# Interfaces.net
KiCad netlist of a schematic drawn in Altium Designer
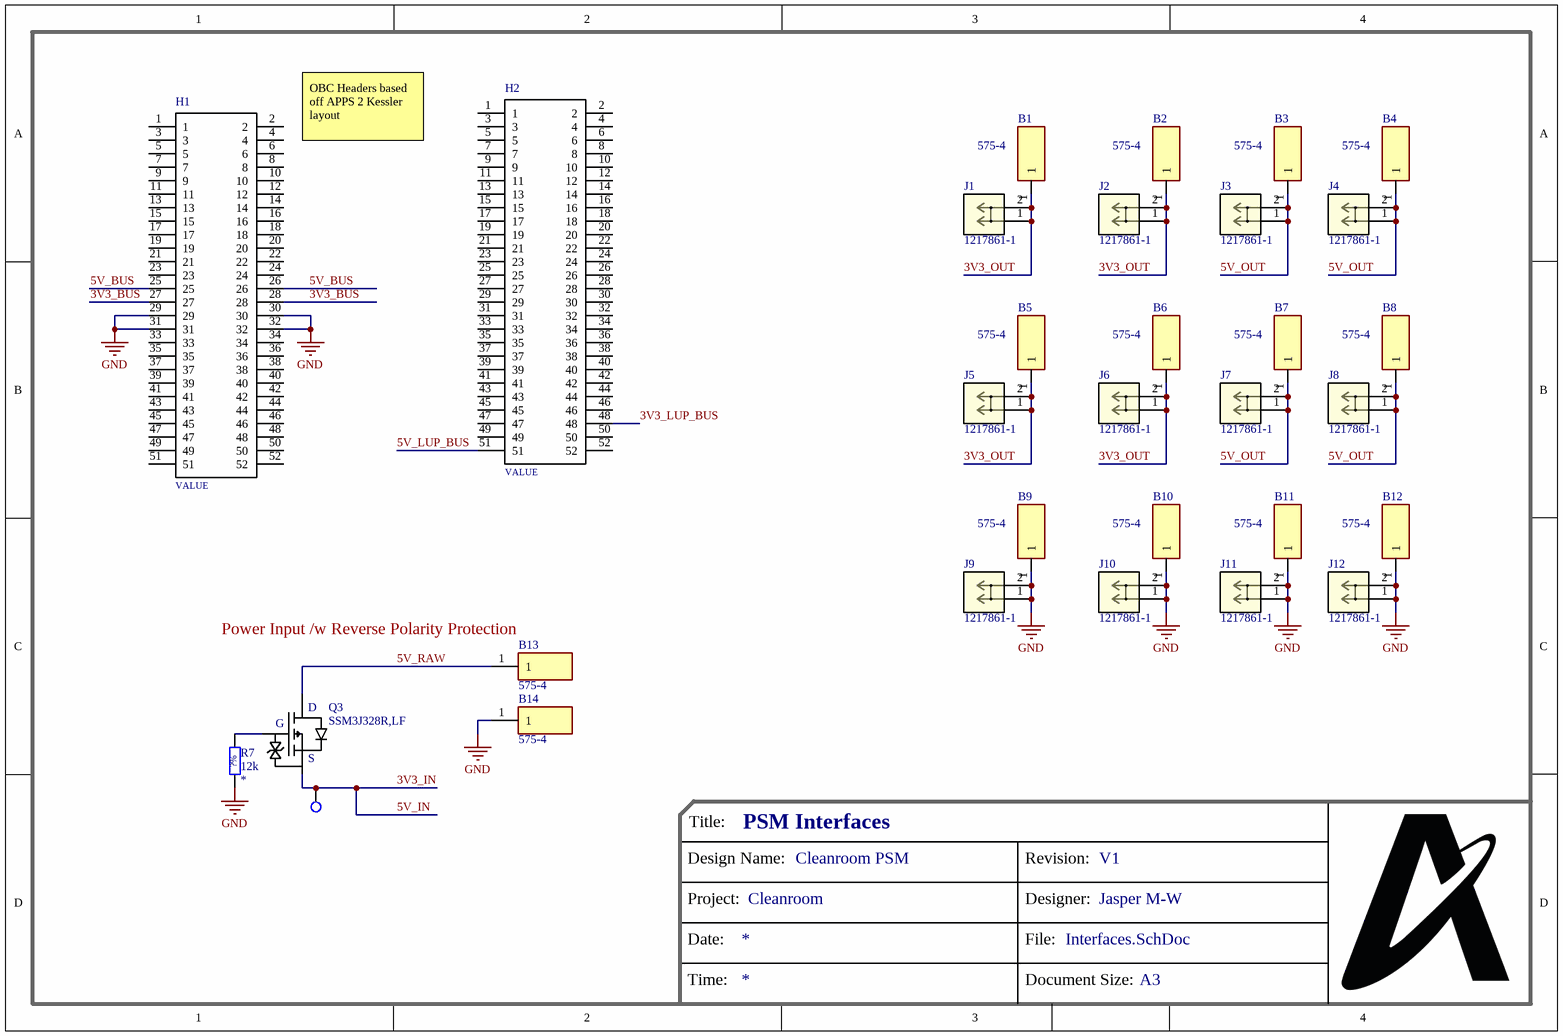
[diagram p0: Interfaces.SchDoc]

(export (version "E")
  (design (tool "Eeschema 10.0.6"))
  (components
    (comp (ref "B1")
      (value "575-4")
      (footprint "5754")
      (description "Test Plugs & Test Jacks NON-INSUL JACK .218\" BRASS NICKEL PLTD")
      (fields (field (name "MOUSER PART NUMBER") "534-575-4"))
      (libsource (lib "575-4") (part "575-4"))
    )
    (comp (ref "B2")
      (value "575-4")
      (footprint "5754")
      (description "Test Plugs & Test Jacks NON-INSUL JACK .218\" BRASS NICKEL PLTD")
      (fields (field (name "MOUSER PART NUMBER") "534-575-4"))
      (libsource (lib "575-4") (part "575-4"))
    )
    (comp (ref "B3")
      (value "575-4")
      (footprint "5754")
      (description "Test Plugs & Test Jacks NON-INSUL JACK .218\" BRASS NICKEL PLTD")
      (fields (field (name "MOUSER PART NUMBER") "534-575-4"))
      (libsource (lib "575-4") (part "575-4"))
    )
    (comp (ref "B4")
      (value "575-4")
      (footprint "5754")
      (description "Test Plugs & Test Jacks NON-INSUL JACK .218\" BRASS NICKEL PLTD")
      (fields (field (name "MOUSER PART NUMBER") "534-575-4"))
      (libsource (lib "575-4") (part "575-4"))
    )
    (comp (ref "B5")
      (value "575-4")
      (footprint "5754")
      (description "Test Plugs & Test Jacks NON-INSUL JACK .218\" BRASS NICKEL PLTD")
      (fields (field (name "MOUSER PART NUMBER") "534-575-4"))
      (libsource (lib "575-4") (part "575-4"))
    )
    (comp (ref "B6")
      (value "575-4")
      (footprint "5754")
      (description "Test Plugs & Test Jacks NON-INSUL JACK .218\" BRASS NICKEL PLTD")
      (fields (field (name "MOUSER PART NUMBER") "534-575-4"))
      (libsource (lib "575-4") (part "575-4"))
    )
    (comp (ref "B7")
      (value "575-4")
      (footprint "5754")
      (description "Test Plugs & Test Jacks NON-INSUL JACK .218\" BRASS NICKEL PLTD")
      (fields (field (name "MOUSER PART NUMBER") "534-575-4"))
      (libsource (lib "575-4") (part "575-4"))
    )
    (comp (ref "B8")
      (value "575-4")
      (footprint "5754")
      (description "Test Plugs & Test Jacks NON-INSUL JACK .218\" BRASS NICKEL PLTD")
      (fields (field (name "MOUSER PART NUMBER") "534-575-4"))
      (libsource (lib "575-4") (part "575-4"))
    )
    (comp (ref "B9")
      (value "575-4")
      (footprint "5754")
      (description "Test Plugs & Test Jacks NON-INSUL JACK .218\" BRASS NICKEL PLTD")
      (fields (field (name "MOUSER PART NUMBER") "534-575-4"))
      (libsource (lib "575-4") (part "575-4"))
    )
    (comp (ref "B10")
      (value "575-4")
      (footprint "5754")
      (description "Test Plugs & Test Jacks NON-INSUL JACK .218\" BRASS NICKEL PLTD")
      (fields (field (name "MOUSER PART NUMBER") "534-575-4"))
      (libsource (lib "575-4") (part "575-4"))
    )
    (comp (ref "B11")
      (value "575-4")
      (footprint "5754")
      (description "Test Plugs & Test Jacks NON-INSUL JACK .218\" BRASS NICKEL PLTD")
      (fields (field (name "MOUSER PART NUMBER") "534-575-4"))
      (libsource (lib "575-4") (part "575-4"))
    )
    (comp (ref "B12")
      (value "575-4")
      (footprint "5754")
      (description "Test Plugs & Test Jacks NON-INSUL JACK .218\" BRASS NICKEL PLTD")
      (fields (field (name "MOUSER PART NUMBER") "534-575-4"))
      (libsource (lib "575-4") (part "575-4"))
    )
    (comp (ref "B13")
      (value "575-4")
      (footprint "5754")
      (description "Test Plugs & Test Jacks NON-INSUL JACK .218\" BRASS NICKEL PLTD")
      (fields (field (name "MOUSER PART NUMBER") "534-575-4"))
      (libsource (lib "") (part "575-4_1"))
    )
    (comp (ref "B14")
      (value "575-4")
      (footprint "5754")
      (description "Test Plugs & Test Jacks NON-INSUL JACK .218\" BRASS NICKEL PLTD")
      (fields (field (name "MOUSER PART NUMBER") "534-575-4"))
      (libsource (lib "") (part "575-4_1"))
    )
    (comp (ref "H1")
      (value "ESQ-126-14-G-D")
      (footprint "*SAMTEC_ESQ-126-14-G-D")
      (fields (field (name "MF") "Samtec Inc."))
      (libsource (lib "ESQ-126-14-G-D") (part "ESQ-126-14-G-D"))
    )
    (comp (ref "H2")
      (value "ESQ-126-14-G-D")
      (footprint "*SAMTEC_ESQ-126-14-G-D")
      (fields (field (name "MF") "Samtec Inc."))
      (libsource (lib "ESQ-126-14-G-D") (part "ESQ-126-14-G-D"))
    )
    (comp (ref "J1")
      (value "1217861-1")
      (footprint "CONN_1217861-1_TEC")
      (description "250 FASTON,PCB TAB,TCBR")
      (fields (field (name "COPYRIGHT") "Copyright (C) 2025 Ultra Librarian. All rights reserved."))
      (libsource (lib "1217861-1") (part "1217861-1"))
    )
    (comp (ref "J2")
      (value "1217861-1")
      (footprint "CONN_1217861-1_TEC")
      (description "250 FASTON,PCB TAB,TCBR")
      (fields (field (name "COPYRIGHT") "Copyright (C) 2025 Ultra Librarian. All rights reserved."))
      (libsource (lib "1217861-1") (part "1217861-1"))
    )
    (comp (ref "J3")
      (value "1217861-1")
      (footprint "CONN_1217861-1_TEC")
      (description "250 FASTON,PCB TAB,TCBR")
      (fields (field (name "COPYRIGHT") "Copyright (C) 2025 Ultra Librarian. All rights reserved."))
      (libsource (lib "1217861-1") (part "1217861-1"))
    )
    (comp (ref "J4")
      (value "1217861-1")
      (footprint "CONN_1217861-1_TEC")
      (description "250 FASTON,PCB TAB,TCBR")
      (fields (field (name "COPYRIGHT") "Copyright (C) 2025 Ultra Librarian. All rights reserved."))
      (libsource (lib "1217861-1") (part "1217861-1"))
    )
    (comp (ref "J5")
      (value "1217861-1")
      (footprint "CONN_1217861-1_TEC")
      (description "250 FASTON,PCB TAB,TCBR")
      (fields (field (name "COPYRIGHT") "Copyright (C) 2025 Ultra Librarian. All rights reserved."))
      (libsource (lib "1217861-1") (part "1217861-1"))
    )
    (comp (ref "J6")
      (value "1217861-1")
      (footprint "CONN_1217861-1_TEC")
      (description "250 FASTON,PCB TAB,TCBR")
      (fields (field (name "COPYRIGHT") "Copyright (C) 2025 Ultra Librarian. All rights reserved."))
      (libsource (lib "1217861-1") (part "1217861-1"))
    )
    (comp (ref "J7")
      (value "1217861-1")
      (footprint "CONN_1217861-1_TEC")
      (description "250 FASTON,PCB TAB,TCBR")
      (fields (field (name "COPYRIGHT") "Copyright (C) 2025 Ultra Librarian. All rights reserved."))
      (libsource (lib "1217861-1") (part "1217861-1"))
    )
    (comp (ref "J8")
      (value "1217861-1")
      (footprint "CONN_1217861-1_TEC")
      (description "250 FASTON,PCB TAB,TCBR")
      (fields (field (name "COPYRIGHT") "Copyright (C) 2025 Ultra Librarian. All rights reserved."))
      (libsource (lib "1217861-1") (part "1217861-1"))
    )
    (comp (ref "J9")
      (value "1217861-1")
      (footprint "CONN_1217861-1_TEC")
      (description "250 FASTON,PCB TAB,TCBR")
      (fields (field (name "COPYRIGHT") "Copyright (C) 2025 Ultra Librarian. All rights reserved."))
      (libsource (lib "1217861-1") (part "1217861-1"))
    )
    (comp (ref "J10")
      (value "1217861-1")
      (footprint "CONN_1217861-1_TEC")
      (description "250 FASTON,PCB TAB,TCBR")
      (fields (field (name "COPYRIGHT") "Copyright (C) 2025 Ultra Librarian. All rights reserved."))
      (libsource (lib "1217861-1") (part "1217861-1"))
    )
    (comp (ref "J11")
      (value "1217861-1")
      (footprint "CONN_1217861-1_TEC")
      (description "250 FASTON,PCB TAB,TCBR")
      (fields (field (name "COPYRIGHT") "Copyright (C) 2025 Ultra Librarian. All rights reserved."))
      (libsource (lib "1217861-1") (part "1217861-1"))
    )
    (comp (ref "J12")
      (value "1217861-1")
      (footprint "CONN_1217861-1_TEC")
      (description "250 FASTON,PCB TAB,TCBR")
      (fields (field (name "COPYRIGHT") "Copyright (C) 2025 Ultra Librarian. All rights reserved."))
      (libsource (lib "1217861-1") (part "1217861-1"))
    )
    (comp (ref "Q3")
      (value "SSM3J328R,LF")
      (footprint "APSS Prototype Parts:SOT23F-3-0.8mm")
      (description "Transistor - MOSFET, P-Channel SSM3J328R,LF")
      (fields (field (name "POWER") "1W") (field (name "APSS STANDARD PART") "APSS Standard"))
      (libsource (lib "APSS Prototype Parts") (part "SSM3J328R,LF"))
    )
    (comp (ref "R7")
      (value "12k")
      (footprint "RESISTOR_0805_2012M-50N")
      (description "Passive - Resistor, Generic")
      (fields (field (name "TOLERANCE") "?%") (field (name "MF PART NO.") "*"))
      (libsource (lib "APSS Generic Components (3)") (part "Generic Resistor"))
    )
    (comp (ref "T1")
      (value "Test Pad")
      (footprint "APSS Generic Components:Test Pad")
      (libsource (lib "APSS Generic Components") (part "Test Pad"))
    )
  )
  (nets
    (net (code "1") (name "/3V3_BUS") (class "Default")
      (node (ref "H1") (pin "27") (pinfunction "27_27") (pintype "passive"))
      (node (ref "H1") (pin "28") (pinfunction "28_28") (pintype "passive"))
    )
    (net (code "2") (name "/3V3_IN") (class "Default")
      (node (ref "Q3") (pin "2") (pinfunction "S_2") (pintype "passive"))
      (node (ref "T1") (pin "1") (pinfunction "0_1") (pintype "passive"))
    )
    (net (code "3") (name "/3V3_LUP_BUS") (class "Default")
      (node (ref "H2") (pin "48") (pinfunction "48_48") (pintype "passive"))
    )
    (net (code "4") (name "/3V3_OUT") (class "Default")
      (node (ref "B1") (pin "1") (pinfunction "1_1") (pintype "passive"))
      (node (ref "B2") (pin "1") (pinfunction "1_1") (pintype "passive"))
      (node (ref "B5") (pin "1") (pinfunction "1_1") (pintype "passive"))
      (node (ref "B6") (pin "1") (pinfunction "1_1") (pintype "passive"))
      (node (ref "J1") (pin "1") (pinfunction "1_1") (pintype "passive"))
      (node (ref "J1") (pin "2") (pinfunction "2_2") (pintype "passive"))
      (node (ref "J2") (pin "1") (pinfunction "1_1") (pintype "passive"))
      (node (ref "J2") (pin "2") (pinfunction "2_2") (pintype "passive"))
      (node (ref "J5") (pin "1") (pinfunction "1_1") (pintype "passive"))
      (node (ref "J5") (pin "2") (pinfunction "2_2") (pintype "passive"))
      (node (ref "J6") (pin "1") (pinfunction "1_1") (pintype "passive"))
      (node (ref "J6") (pin "2") (pinfunction "2_2") (pintype "passive"))
    )
    (net (code "5") (name "/5V_BUS") (class "Default")
      (node (ref "H1") (pin "25") (pinfunction "25_25") (pintype "passive"))
      (node (ref "H1") (pin "26") (pinfunction "26_26") (pintype "passive"))
    )
    (net (code "6") (name "/5V_LUP_BUS") (class "Default")
      (node (ref "H2") (pin "51") (pinfunction "51_51") (pintype "passive"))
    )
    (net (code "7") (name "/5V_OUT") (class "Default")
      (node (ref "B3") (pin "1") (pinfunction "1_1") (pintype "passive"))
      (node (ref "B4") (pin "1") (pinfunction "1_1") (pintype "passive"))
      (node (ref "B7") (pin "1") (pinfunction "1_1") (pintype "passive"))
      (node (ref "B8") (pin "1") (pinfunction "1_1") (pintype "passive"))
      (node (ref "J3") (pin "1") (pinfunction "1_1") (pintype "passive"))
      (node (ref "J3") (pin "2") (pinfunction "2_2") (pintype "passive"))
      (node (ref "J4") (pin "1") (pinfunction "1_1") (pintype "passive"))
      (node (ref "J4") (pin "2") (pinfunction "2_2") (pintype "passive"))
      (node (ref "J7") (pin "1") (pinfunction "1_1") (pintype "passive"))
      (node (ref "J7") (pin "2") (pinfunction "2_2") (pintype "passive"))
      (node (ref "J8") (pin "1") (pinfunction "1_1") (pintype "passive"))
      (node (ref "J8") (pin "2") (pinfunction "2_2") (pintype "passive"))
    )
    (net (code "8") (name "/5V_RAW") (class "Default")
      (node (ref "B13") (pin "1") (pinfunction "1_1") (pintype "passive"))
      (node (ref "Q3") (pin "3") (pinfunction "D_3") (pintype "passive"))
    )
    (net (code "9") (name "GND") (class "Default")
      (node (ref "B10") (pin "1") (pinfunction "1_1") (pintype "passive"))
      (node (ref "B11") (pin "1") (pinfunction "1_1") (pintype "passive"))
      (node (ref "B12") (pin "1") (pinfunction "1_1") (pintype "passive"))
      (node (ref "B14") (pin "1") (pinfunction "1_1") (pintype "passive"))
      (node (ref "B9") (pin "1") (pinfunction "1_1") (pintype "passive"))
      (node (ref "H1") (pin "29") (pinfunction "29_29") (pintype "passive"))
      (node (ref "H1") (pin "30") (pinfunction "30_30") (pintype "passive"))
      (node (ref "H1") (pin "31") (pinfunction "31_31") (pintype "passive"))
      (node (ref "H1") (pin "32") (pinfunction "32_32") (pintype "passive"))
      (node (ref "J10") (pin "1") (pinfunction "1_1") (pintype "passive"))
      (node (ref "J10") (pin "2") (pinfunction "2_2") (pintype "passive"))
      (node (ref "J11") (pin "1") (pinfunction "1_1") (pintype "passive"))
      (node (ref "J11") (pin "2") (pinfunction "2_2") (pintype "passive"))
      (node (ref "J12") (pin "1") (pinfunction "1_1") (pintype "passive"))
      (node (ref "J12") (pin "2") (pinfunction "2_2") (pintype "passive"))
      (node (ref "J9") (pin "1") (pinfunction "1_1") (pintype "passive"))
      (node (ref "J9") (pin "2") (pinfunction "2_2") (pintype "passive"))
      (node (ref "R7") (pin "1") (pinfunction "1_1") (pintype "passive"))
    )
    (net (code "10") (name "Net-(Q3-G)") (class "Default")
      (node (ref "Q3") (pin "1") (pinfunction "G_1") (pintype "passive"))
      (node (ref "R7") (pin "2") (pinfunction "2_2") (pintype "passive"))
    )
    (net (code "11") (name "unconnected-(H1-Pad1)") (class "Default")
      (node (ref "H1") (pin "1") (pinfunction "1_1") (pintype "passive"))
    )
    (net (code "12") (name "unconnected-(H1-Pad2)") (class "Default")
      (node (ref "H1") (pin "2") (pinfunction "2_2") (pintype "passive"))
    )
    (net (code "13") (name "unconnected-(H1-Pad3)") (class "Default")
      (node (ref "H1") (pin "3") (pinfunction "3_3") (pintype "passive"))
    )
    (net (code "14") (name "unconnected-(H1-Pad4)") (class "Default")
      (node (ref "H1") (pin "4") (pinfunction "4_4") (pintype "passive"))
    )
    (net (code "15") (name "unconnected-(H1-Pad5)") (class "Default")
      (node (ref "H1") (pin "5") (pinfunction "5_5") (pintype "passive"))
    )
    (net (code "16") (name "unconnected-(H1-Pad6)") (class "Default")
      (node (ref "H1") (pin "6") (pinfunction "6_6") (pintype "passive"))
    )
    (net (code "17") (name "unconnected-(H1-Pad7)") (class "Default")
      (node (ref "H1") (pin "7") (pinfunction "7_7") (pintype "passive"))
    )
    (net (code "18") (name "unconnected-(H1-Pad8)") (class "Default")
      (node (ref "H1") (pin "8") (pinfunction "8_8") (pintype "passive"))
    )
    (net (code "19") (name "unconnected-(H1-Pad9)") (class "Default")
      (node (ref "H1") (pin "9") (pinfunction "9_9") (pintype "passive"))
    )
    (net (code "20") (name "unconnected-(H1-Pad10)") (class "Default")
      (node (ref "H1") (pin "10") (pinfunction "10_10") (pintype "passive"))
    )
    (net (code "21") (name "unconnected-(H1-Pad11)") (class "Default")
      (node (ref "H1") (pin "11") (pinfunction "11_11") (pintype "passive"))
    )
    (net (code "22") (name "unconnected-(H1-Pad12)") (class "Default")
      (node (ref "H1") (pin "12") (pinfunction "12_12") (pintype "passive"))
    )
    (net (code "23") (name "unconnected-(H1-Pad13)") (class "Default")
      (node (ref "H1") (pin "13") (pinfunction "13_13") (pintype "passive"))
    )
    (net (code "24") (name "unconnected-(H1-Pad14)") (class "Default")
      (node (ref "H1") (pin "14") (pinfunction "14_14") (pintype "passive"))
    )
    (net (code "25") (name "unconnected-(H1-Pad15)") (class "Default")
      (node (ref "H1") (pin "15") (pinfunction "15_15") (pintype "passive"))
    )
    (net (code "26") (name "unconnected-(H1-Pad16)") (class "Default")
      (node (ref "H1") (pin "16") (pinfunction "16_16") (pintype "passive"))
    )
    (net (code "27") (name "unconnected-(H1-Pad17)") (class "Default")
      (node (ref "H1") (pin "17") (pinfunction "17_17") (pintype "passive"))
    )
    (net (code "28") (name "unconnected-(H1-Pad18)") (class "Default")
      (node (ref "H1") (pin "18") (pinfunction "18_18") (pintype "passive"))
    )
    (net (code "29") (name "unconnected-(H1-Pad19)") (class "Default")
      (node (ref "H1") (pin "19") (pinfunction "19_19") (pintype "passive"))
    )
    (net (code "30") (name "unconnected-(H1-Pad20)") (class "Default")
      (node (ref "H1") (pin "20") (pinfunction "20_20") (pintype "passive"))
    )
    (net (code "31") (name "unconnected-(H1-Pad21)") (class "Default")
      (node (ref "H1") (pin "21") (pinfunction "21_21") (pintype "passive"))
    )
    (net (code "32") (name "unconnected-(H1-Pad22)") (class "Default")
      (node (ref "H1") (pin "22") (pinfunction "22_22") (pintype "passive"))
    )
    (net (code "33") (name "unconnected-(H1-Pad23)") (class "Default")
      (node (ref "H1") (pin "23") (pinfunction "23_23") (pintype "passive"))
    )
    (net (code "34") (name "unconnected-(H1-Pad24)") (class "Default")
      (node (ref "H1") (pin "24") (pinfunction "24_24") (pintype "passive"))
    )
    (net (code "35") (name "unconnected-(H1-Pad33)") (class "Default")
      (node (ref "H1") (pin "33") (pinfunction "33_33") (pintype "passive"))
    )
    (net (code "36") (name "unconnected-(H1-Pad34)") (class "Default")
      (node (ref "H1") (pin "34") (pinfunction "34_34") (pintype "passive"))
    )
    (net (code "37") (name "unconnected-(H1-Pad35)") (class "Default")
      (node (ref "H1") (pin "35") (pinfunction "35_35") (pintype "passive"))
    )
    (net (code "38") (name "unconnected-(H1-Pad36)") (class "Default")
      (node (ref "H1") (pin "36") (pinfunction "36_36") (pintype "passive"))
    )
    (net (code "39") (name "unconnected-(H1-Pad37)") (class "Default")
      (node (ref "H1") (pin "37") (pinfunction "37_37") (pintype "passive"))
    )
    (net (code "40") (name "unconnected-(H1-Pad38)") (class "Default")
      (node (ref "H1") (pin "38") (pinfunction "38_38") (pintype "passive"))
    )
    (net (code "41") (name "unconnected-(H1-Pad39)") (class "Default")
      (node (ref "H1") (pin "39") (pinfunction "39_39") (pintype "passive"))
    )
    (net (code "42") (name "unconnected-(H1-Pad40)") (class "Default")
      (node (ref "H1") (pin "40") (pinfunction "40_40") (pintype "passive"))
    )
    (net (code "43") (name "unconnected-(H1-Pad41)") (class "Default")
      (node (ref "H1") (pin "41") (pinfunction "41_41") (pintype "passive"))
    )
    (net (code "44") (name "unconnected-(H1-Pad42)") (class "Default")
      (node (ref "H1") (pin "42") (pinfunction "42_42") (pintype "passive"))
    )
    (net (code "45") (name "unconnected-(H1-Pad43)") (class "Default")
      (node (ref "H1") (pin "43") (pinfunction "43_43") (pintype "passive"))
    )
    (net (code "46") (name "unconnected-(H1-Pad44)") (class "Default")
      (node (ref "H1") (pin "44") (pinfunction "44_44") (pintype "passive"))
    )
    (net (code "47") (name "unconnected-(H1-Pad45)") (class "Default")
      (node (ref "H1") (pin "45") (pinfunction "45_45") (pintype "passive"))
    )
    (net (code "48") (name "unconnected-(H1-Pad46)") (class "Default")
      (node (ref "H1") (pin "46") (pinfunction "46_46") (pintype "passive"))
    )
    (net (code "49") (name "unconnected-(H1-Pad47)") (class "Default")
      (node (ref "H1") (pin "47") (pinfunction "47_47") (pintype "passive"))
    )
    (net (code "50") (name "unconnected-(H1-Pad48)") (class "Default")
      (node (ref "H1") (pin "48") (pinfunction "48_48") (pintype "passive"))
    )
    (net (code "51") (name "unconnected-(H1-Pad49)") (class "Default")
      (node (ref "H1") (pin "49") (pinfunction "49_49") (pintype "passive"))
    )
    (net (code "52") (name "unconnected-(H1-Pad50)") (class "Default")
      (node (ref "H1") (pin "50") (pinfunction "50_50") (pintype "passive"))
    )
    (net (code "53") (name "unconnected-(H1-Pad51)") (class "Default")
      (node (ref "H1") (pin "51") (pinfunction "51_51") (pintype "passive"))
    )
    (net (code "54") (name "unconnected-(H1-Pad52)") (class "Default")
      (node (ref "H1") (pin "52") (pinfunction "52_52") (pintype "passive"))
    )
    (net (code "55") (name "unconnected-(H2-Pad1)") (class "Default")
      (node (ref "H2") (pin "1") (pinfunction "1_1") (pintype "passive"))
    )
    (net (code "56") (name "unconnected-(H2-Pad2)") (class "Default")
      (node (ref "H2") (pin "2") (pinfunction "2_2") (pintype "passive"))
    )
    (net (code "57") (name "unconnected-(H2-Pad3)") (class "Default")
      (node (ref "H2") (pin "3") (pinfunction "3_3") (pintype "passive"))
    )
    (net (code "58") (name "unconnected-(H2-Pad4)") (class "Default")
      (node (ref "H2") (pin "4") (pinfunction "4_4") (pintype "passive"))
    )
    (net (code "59") (name "unconnected-(H2-Pad5)") (class "Default")
      (node (ref "H2") (pin "5") (pinfunction "5_5") (pintype "passive"))
    )
    (net (code "60") (name "unconnected-(H2-Pad6)") (class "Default")
      (node (ref "H2") (pin "6") (pinfunction "6_6") (pintype "passive"))
    )
    (net (code "61") (name "unconnected-(H2-Pad7)") (class "Default")
      (node (ref "H2") (pin "7") (pinfunction "7_7") (pintype "passive"))
    )
    (net (code "62") (name "unconnected-(H2-Pad8)") (class "Default")
      (node (ref "H2") (pin "8") (pinfunction "8_8") (pintype "passive"))
    )
    (net (code "63") (name "unconnected-(H2-Pad9)") (class "Default")
      (node (ref "H2") (pin "9") (pinfunction "9_9") (pintype "passive"))
    )
    (net (code "64") (name "unconnected-(H2-Pad10)") (class "Default")
      (node (ref "H2") (pin "10") (pinfunction "10_10") (pintype "passive"))
    )
    (net (code "65") (name "unconnected-(H2-Pad11)") (class "Default")
      (node (ref "H2") (pin "11") (pinfunction "11_11") (pintype "passive"))
    )
    (net (code "66") (name "unconnected-(H2-Pad12)") (class "Default")
      (node (ref "H2") (pin "12") (pinfunction "12_12") (pintype "passive"))
    )
    (net (code "67") (name "unconnected-(H2-Pad13)") (class "Default")
      (node (ref "H2") (pin "13") (pinfunction "13_13") (pintype "passive"))
    )
    (net (code "68") (name "unconnected-(H2-Pad14)") (class "Default")
      (node (ref "H2") (pin "14") (pinfunction "14_14") (pintype "passive"))
    )
    (net (code "69") (name "unconnected-(H2-Pad15)") (class "Default")
      (node (ref "H2") (pin "15") (pinfunction "15_15") (pintype "passive"))
    )
    (net (code "70") (name "unconnected-(H2-Pad16)") (class "Default")
      (node (ref "H2") (pin "16") (pinfunction "16_16") (pintype "passive"))
    )
    (net (code "71") (name "unconnected-(H2-Pad17)") (class "Default")
      (node (ref "H2") (pin "17") (pinfunction "17_17") (pintype "passive"))
    )
    (net (code "72") (name "unconnected-(H2-Pad18)") (class "Default")
      (node (ref "H2") (pin "18") (pinfunction "18_18") (pintype "passive"))
    )
    (net (code "73") (name "unconnected-(H2-Pad19)") (class "Default")
      (node (ref "H2") (pin "19") (pinfunction "19_19") (pintype "passive"))
    )
    (net (code "74") (name "unconnected-(H2-Pad20)") (class "Default")
      (node (ref "H2") (pin "20") (pinfunction "20_20") (pintype "passive"))
    )
    (net (code "75") (name "unconnected-(H2-Pad21)") (class "Default")
      (node (ref "H2") (pin "21") (pinfunction "21_21") (pintype "passive"))
    )
    (net (code "76") (name "unconnected-(H2-Pad22)") (class "Default")
      (node (ref "H2") (pin "22") (pinfunction "22_22") (pintype "passive"))
    )
    (net (code "77") (name "unconnected-(H2-Pad23)") (class "Default")
      (node (ref "H2") (pin "23") (pinfunction "23_23") (pintype "passive"))
    )
    (net (code "78") (name "unconnected-(H2-Pad24)") (class "Default")
      (node (ref "H2") (pin "24") (pinfunction "24_24") (pintype "passive"))
    )
    (net (code "79") (name "unconnected-(H2-Pad25)") (class "Default")
      (node (ref "H2") (pin "25") (pinfunction "25_25") (pintype "passive"))
    )
    (net (code "80") (name "unconnected-(H2-Pad26)") (class "Default")
      (node (ref "H2") (pin "26") (pinfunction "26_26") (pintype "passive"))
    )
    (net (code "81") (name "unconnected-(H2-Pad27)") (class "Default")
      (node (ref "H2") (pin "27") (pinfunction "27_27") (pintype "passive"))
    )
    (net (code "82") (name "unconnected-(H2-Pad28)") (class "Default")
      (node (ref "H2") (pin "28") (pinfunction "28_28") (pintype "passive"))
    )
    (net (code "83") (name "unconnected-(H2-Pad29)") (class "Default")
      (node (ref "H2") (pin "29") (pinfunction "29_29") (pintype "passive"))
    )
    (net (code "84") (name "unconnected-(H2-Pad30)") (class "Default")
      (node (ref "H2") (pin "30") (pinfunction "30_30") (pintype "passive"))
    )
    (net (code "85") (name "unconnected-(H2-Pad31)") (class "Default")
      (node (ref "H2") (pin "31") (pinfunction "31_31") (pintype "passive"))
    )
    (net (code "86") (name "unconnected-(H2-Pad32)") (class "Default")
      (node (ref "H2") (pin "32") (pinfunction "32_32") (pintype "passive"))
    )
    (net (code "87") (name "unconnected-(H2-Pad33)") (class "Default")
      (node (ref "H2") (pin "33") (pinfunction "33_33") (pintype "passive"))
    )
    (net (code "88") (name "unconnected-(H2-Pad34)") (class "Default")
      (node (ref "H2") (pin "34") (pinfunction "34_34") (pintype "passive"))
    )
    (net (code "89") (name "unconnected-(H2-Pad35)") (class "Default")
      (node (ref "H2") (pin "35") (pinfunction "35_35") (pintype "passive"))
    )
    (net (code "90") (name "unconnected-(H2-Pad36)") (class "Default")
      (node (ref "H2") (pin "36") (pinfunction "36_36") (pintype "passive"))
    )
    (net (code "91") (name "unconnected-(H2-Pad37)") (class "Default")
      (node (ref "H2") (pin "37") (pinfunction "37_37") (pintype "passive"))
    )
    (net (code "92") (name "unconnected-(H2-Pad38)") (class "Default")
      (node (ref "H2") (pin "38") (pinfunction "38_38") (pintype "passive"))
    )
    (net (code "93") (name "unconnected-(H2-Pad39)") (class "Default")
      (node (ref "H2") (pin "39") (pinfunction "39_39") (pintype "passive"))
    )
    (net (code "94") (name "unconnected-(H2-Pad40)") (class "Default")
      (node (ref "H2") (pin "40") (pinfunction "40_40") (pintype "passive"))
    )
    (net (code "95") (name "unconnected-(H2-Pad41)") (class "Default")
      (node (ref "H2") (pin "41") (pinfunction "41_41") (pintype "passive"))
    )
    (net (code "96") (name "unconnected-(H2-Pad42)") (class "Default")
      (node (ref "H2") (pin "42") (pinfunction "42_42") (pintype "passive"))
    )
    (net (code "97") (name "unconnected-(H2-Pad43)") (class "Default")
      (node (ref "H2") (pin "43") (pinfunction "43_43") (pintype "passive"))
    )
    (net (code "98") (name "unconnected-(H2-Pad44)") (class "Default")
      (node (ref "H2") (pin "44") (pinfunction "44_44") (pintype "passive"))
    )
    (net (code "99") (name "unconnected-(H2-Pad45)") (class "Default")
      (node (ref "H2") (pin "45") (pinfunction "45_45") (pintype "passive"))
    )
    (net (code "100") (name "unconnected-(H2-Pad46)") (class "Default")
      (node (ref "H2") (pin "46") (pinfunction "46_46") (pintype "passive"))
    )
    (net (code "101") (name "unconnected-(H2-Pad47)") (class "Default")
      (node (ref "H2") (pin "47") (pinfunction "47_47") (pintype "passive"))
    )
    (net (code "102") (name "unconnected-(H2-Pad49)") (class "Default")
      (node (ref "H2") (pin "49") (pinfunction "49_49") (pintype "passive"))
    )
    (net (code "103") (name "unconnected-(H2-Pad50)") (class "Default")
      (node (ref "H2") (pin "50") (pinfunction "50_50") (pintype "passive"))
    )
    (net (code "104") (name "unconnected-(H2-Pad52)") (class "Default")
      (node (ref "H2") (pin "52") (pinfunction "52_52") (pintype "passive"))
    )
  )
)
